# driverMotor.net
KiCad netlist of a schematic drawn in EAGLE
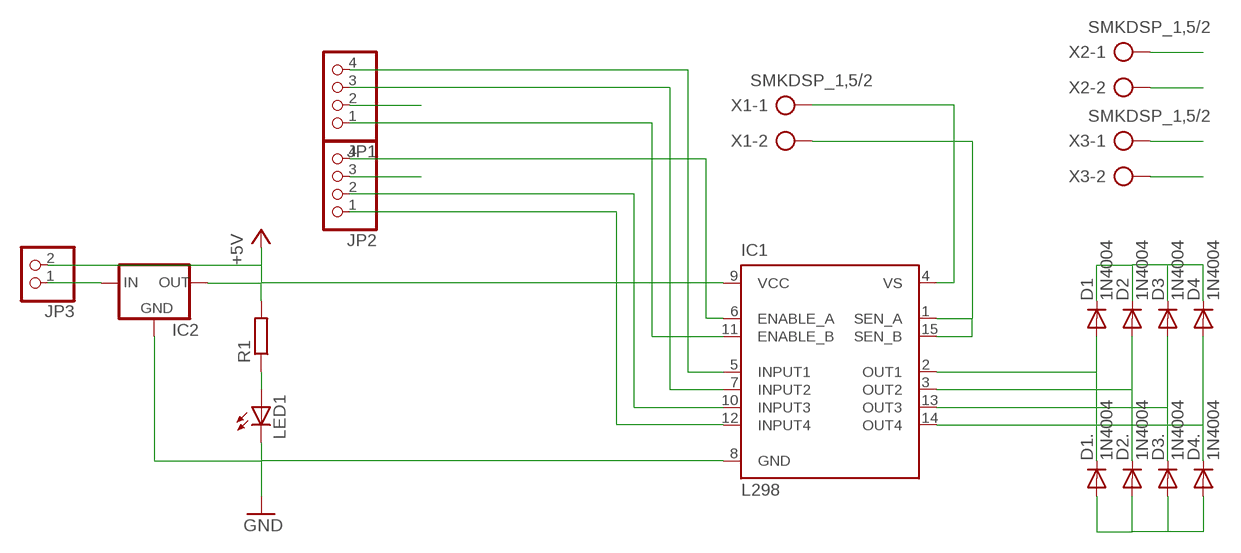
[diagram p0: schematic, sheet 1]

(export (version "E")
  (design (tool "Eeschema 10.0.6"))
  (components
    (comp (ref "D1")
      (value "1N4004")
      (footprint "eagle-import:DO41-10")
      (libsource (lib "eagle-import") (part "1N4004"))
    )
    (comp (ref "D1.")
      (value "1N4004")
      (footprint "eagle-import:DO41-10")
      (libsource (lib "eagle-import") (part "1N4004"))
    )
    (comp (ref "D2")
      (value "1N4004")
      (footprint "eagle-import:DO41-10")
      (libsource (lib "eagle-import") (part "1N4004"))
    )
    (comp (ref "D2.")
      (value "1N4004")
      (footprint "eagle-import:DO41-10")
      (libsource (lib "eagle-import") (part "1N4004"))
    )
    (comp (ref "D3")
      (value "1N4004")
      (footprint "eagle-import:DO41-10")
      (libsource (lib "eagle-import") (part "1N4004"))
    )
    (comp (ref "D3.")
      (value "1N4004")
      (footprint "eagle-import:DO41-10")
      (libsource (lib "eagle-import") (part "1N4004"))
    )
    (comp (ref "D4")
      (value "1N4004")
      (footprint "eagle-import:DO41-10")
      (libsource (lib "eagle-import") (part "1N4004"))
    )
    (comp (ref "D4.")
      (value "1N4004")
      (footprint "eagle-import:DO41-10")
      (libsource (lib "eagle-import") (part "1N4004"))
    )
    (comp (ref "IC1")
      (value "L298")
      (footprint "eagle-import:MULTIWATT-15")
      (libsource (lib "eagle-import") (part "L298"))
    )
    (comp (ref "IC2")
      (value "78MXXS")
      (footprint "eagle-import:78MXXS")
      (libsource (lib "eagle-import") (part "78MXXS"))
    )
    (comp (ref "JP1")
      (value "PINHD-1X4")
      (footprint "eagle-import:1X04")
      (libsource (lib "eagle-import") (part "PINHD-1X4"))
    )
    (comp (ref "JP2")
      (value "PINHD-1X4")
      (footprint "eagle-import:1X04")
      (libsource (lib "eagle-import") (part "PINHD-1X4"))
    )
    (comp (ref "JP3")
      (value "PINHD-1X2")
      (footprint "eagle-import:1X02")
      (libsource (lib "eagle-import") (part "PINHD-1X2"))
    )
    (comp (ref "LED1")
      (value "LED5MM")
      (footprint "eagle-import:LED5MM")
      (libsource (lib "eagle-import") (part "LED5MM"))
    )
    (comp (ref "R1")
      (value "R-EU_0411/12")
      (footprint "eagle-import:0411_12")
      (libsource (lib "eagle-import") (part "R-EU_0411/12"))
    )
    (comp (ref "X1")
      (value "SMKDSP_1,5/2")
      (footprint "eagle-import:SMKDSP_1,5_2")
      (fields (field (name "MF") "FARNELL") (field (name "MPN") "1733570"))
      (libsource (lib "eagle-import") (part "SMKDSP_1,5/2"))
    )
    (comp (ref "X2")
      (value "SMKDSP_1,5/2")
      (footprint "eagle-import:SMKDSP_1,5_2")
      (fields (field (name "MF") "FARNELL") (field (name "MPN") "1733570"))
      (libsource (lib "eagle-import") (part "SMKDSP_1,5/2"))
    )
    (comp (ref "X3")
      (value "SMKDSP_1,5/2")
      (footprint "eagle-import:SMKDSP_1,5_2")
      (fields (field (name "MF") "FARNELL") (field (name "MPN") "1733570"))
      (libsource (lib "eagle-import") (part "SMKDSP_1,5/2"))
    )
  )
  (nets
    (net (code "1") (name "+5V") (class "Default")
      (node (ref "IC1") (pin "9") (pinfunction "VCC_9") (pintype "power_in"))
      (node (ref "IC2") (pin "OUT") (pinfunction "OUT_OUT") (pintype "passive"))
      (node (ref "JP1") (pin "2") (pinfunction "2_2") (pintype "passive"))
      (node (ref "JP3") (pin "2") (pinfunction "2_2") (pintype "passive"))
      (node (ref "R1") (pin "2") (pinfunction "2_2") (pintype "passive"))
    )
    (net (code "2") (name "/MOTOR1_1") (class "Default")
      (node (ref "D1") (pin "A") (pinfunction "A_A") (pintype "passive"))
      (node (ref "D1.") (pin "C") (pinfunction "C_C") (pintype "passive"))
      (node (ref "IC1") (pin "2") (pinfunction "OUT1_2") (pintype "output"))
      (node (ref "X2") (pin "1") (pinfunction "KL_1") (pintype "passive"))
    )
    (net (code "3") (name "/MOTOR1_2") (class "Default")
      (node (ref "D2") (pin "A") (pinfunction "A_A") (pintype "passive"))
      (node (ref "D2.") (pin "C") (pinfunction "C_C") (pintype "passive"))
      (node (ref "IC1") (pin "3") (pinfunction "OUT2_3") (pintype "output"))
      (node (ref "X2") (pin "2") (pinfunction "KL_2") (pintype "passive"))
    )
    (net (code "4") (name "/MOTOR2_1") (class "Default")
      (node (ref "D3") (pin "A") (pinfunction "A_A") (pintype "passive"))
      (node (ref "D3.") (pin "C") (pinfunction "C_C") (pintype "passive"))
      (node (ref "IC1") (pin "13") (pinfunction "OUT3_13") (pintype "output"))
      (node (ref "X3") (pin "1") (pinfunction "KL_1") (pintype "passive"))
    )
    (net (code "5") (name "/MOTOR2_2") (class "Default")
      (node (ref "D4") (pin "A") (pinfunction "A_A") (pintype "passive"))
      (node (ref "D4.") (pin "C") (pinfunction "C_C") (pintype "passive"))
      (node (ref "IC1") (pin "14") (pinfunction "OUT4_14") (pintype "output"))
      (node (ref "X3") (pin "2") (pinfunction "KL_2") (pintype "passive"))
    )
    (net (code "6") (name "/VS") (class "Default")
      (node (ref "D1") (pin "C") (pinfunction "C_C") (pintype "passive"))
      (node (ref "D2") (pin "C") (pinfunction "C_C") (pintype "passive"))
      (node (ref "D3") (pin "C") (pinfunction "C_C") (pintype "passive"))
      (node (ref "D4") (pin "C") (pinfunction "C_C") (pintype "passive"))
      (node (ref "IC1") (pin "4") (pinfunction "VS_4") (pintype "power_in"))
      (node (ref "IC2") (pin "IN") (pinfunction "IN_IN") (pintype "input"))
      (node (ref "JP3") (pin "1") (pinfunction "1_1") (pintype "passive"))
      (node (ref "X1") (pin "1") (pinfunction "KL_1") (pintype "passive"))
    )
    (net (code "7") (name "GND") (class "Default")
      (node (ref "D1.") (pin "A") (pinfunction "A_A") (pintype "passive"))
      (node (ref "D2.") (pin "A") (pinfunction "A_A") (pintype "passive"))
      (node (ref "D3.") (pin "A") (pinfunction "A_A") (pintype "passive"))
      (node (ref "D4.") (pin "A") (pinfunction "A_A") (pintype "passive"))
      (node (ref "IC1") (pin "1") (pinfunction "SEN_A_1") (pintype "input"))
      (node (ref "IC1") (pin "15") (pinfunction "SEN_B_15") (pintype "input"))
      (node (ref "IC1") (pin "8") (pinfunction "GND_8") (pintype "power_in"))
      (node (ref "IC2") (pin "GND") (pinfunction "GND_GND") (pintype "input"))
      (node (ref "JP2") (pin "3") (pinfunction "3_3") (pintype "passive"))
      (node (ref "LED1") (pin "K") (pinfunction "C_K") (pintype "passive"))
      (node (ref "X1") (pin "2") (pinfunction "KL_2") (pintype "passive"))
    )
    (net (code "8") (name "Net-(IC1-ENABLE_A)") (class "Default")
      (node (ref "IC1") (pin "6") (pinfunction "ENABLE_A_6") (pintype "input"))
      (node (ref "JP2") (pin "4") (pinfunction "4_4") (pintype "passive"))
    )
    (net (code "9") (name "Net-(IC1-ENABLE_B)") (class "Default")
      (node (ref "IC1") (pin "11") (pinfunction "ENABLE_B_11") (pintype "input"))
      (node (ref "JP1") (pin "1") (pinfunction "1_1") (pintype "passive"))
    )
    (net (code "10") (name "Net-(IC1-INPUT1)") (class "Default")
      (node (ref "IC1") (pin "5") (pinfunction "INPUT1_5") (pintype "input"))
      (node (ref "JP1") (pin "4") (pinfunction "4_4") (pintype "passive"))
    )
    (net (code "11") (name "Net-(IC1-INPUT2)") (class "Default")
      (node (ref "IC1") (pin "7") (pinfunction "INPUT2_7") (pintype "input"))
      (node (ref "JP1") (pin "3") (pinfunction "3_3") (pintype "passive"))
    )
    (net (code "12") (name "Net-(IC1-INPUT3)") (class "Default")
      (node (ref "IC1") (pin "10") (pinfunction "INPUT3_10") (pintype "input"))
      (node (ref "JP2") (pin "2") (pinfunction "2_2") (pintype "passive"))
    )
    (net (code "13") (name "Net-(IC1-INPUT4)") (class "Default")
      (node (ref "IC1") (pin "12") (pinfunction "INPUT4_12") (pintype "input"))
      (node (ref "JP2") (pin "1") (pinfunction "1_1") (pintype "passive"))
    )
    (net (code "14") (name "Net-(LED1-PadA)") (class "Default")
      (node (ref "LED1") (pin "A") (pinfunction "A_A") (pintype "passive"))
      (node (ref "R1") (pin "1") (pinfunction "1_1") (pintype "passive"))
    )
  )
)
